# heat.net
KiCad netlist of a schematic drawn in Altium Designer
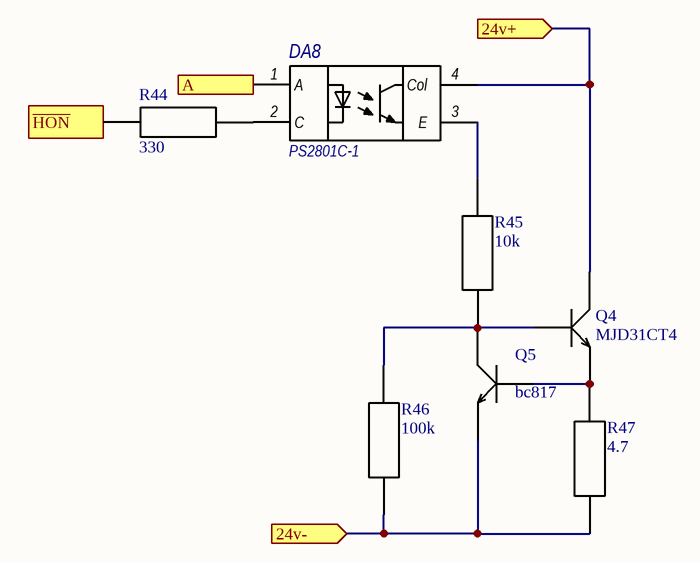
[diagram p0: heat.SchDoc]

(export (version "E")
  (design (tool "Eeschema 10.0.6"))
  (components
    (comp (ref "DA8")
      (value "PS2801C-1")
      (footprint "SSOP-4N")
      (fields (field (name "TYPE") "PS2801C-1"))
      (libsource (lib "Optocoupler") (part "PS2801C-1"))
    )
    (comp (ref "Q4")
      (value "MJD31CT4")
      (footprint "d-pak")
      (description "bc817")
      (libsource (lib "lib") (part "npn"))
    )
    (comp (ref "Q5") (value "bc817") (footprint "sot23") (libsource (lib "lib") (part "npn")))
    (comp (ref "R44") (value "330") (footprint "res_0402") (libsource (lib "lib") (part "res")))
    (comp (ref "R45") (value "10k") (footprint "Lib:0805-res") (libsource (lib "lib") (part "res")))
    (comp (ref "R46") (value "100k") (footprint "Lib:0805-res") (libsource (lib "lib") (part "res")))
    (comp (ref "R47") (value "4.7") (footprint "2512_res") (libsource (lib "lib") (part "res")))
  )
  (nets
    (net (code "1") (name "/24v+") (class "Default")
      (node (ref "DA8") (pin "4") (pinfunction "Col_4") (pintype "passive"))
      (node (ref "Q4") (pin "2") (pinfunction "K_2") (pintype "passive"))
    )
    (net (code "2") (name "/24v-") (class "Default")
      (node (ref "Q5") (pin "3") (pinfunction "E_3") (pintype "passive"))
      (node (ref "R46") (pin "1") (pinfunction "1_1") (pintype "passive"))
      (node (ref "R47") (pin "1") (pinfunction "1_1") (pintype "passive"))
    )
    (net (code "3") (name "/A") (class "Default")
      (node (ref "DA8") (pin "1") (pinfunction "A_1") (pintype "passive"))
    )
    (net (code "4") (name "/~{HON}") (class "Default")
      (node (ref "R44") (pin "1") (pinfunction "1_1") (pintype "passive"))
    )
    (net (code "5") (name "Net-(DA8-C)") (class "Default")
      (node (ref "DA8") (pin "2") (pinfunction "C_2") (pintype "passive"))
      (node (ref "R44") (pin "2") (pinfunction "2_2") (pintype "passive"))
    )
    (net (code "6") (name "Net-(DA8-E)") (class "Default")
      (node (ref "DA8") (pin "3") (pinfunction "E_3") (pintype "passive"))
      (node (ref "R45") (pin "2") (pinfunction "2_2") (pintype "passive"))
    )
    (net (code "7") (name "Net-(Q4-B)") (class "Default")
      (node (ref "Q4") (pin "1") (pinfunction "B_1") (pintype "passive"))
      (node (ref "Q5") (pin "2") (pinfunction "K_2") (pintype "passive"))
      (node (ref "R45") (pin "1") (pinfunction "1_1") (pintype "passive"))
      (node (ref "R46") (pin "2") (pinfunction "2_2") (pintype "passive"))
    )
    (net (code "8") (name "Net-(Q4-E)") (class "Default")
      (node (ref "Q4") (pin "3") (pinfunction "E_3") (pintype "passive"))
      (node (ref "Q5") (pin "1") (pinfunction "B_1") (pintype "passive"))
      (node (ref "R47") (pin "2") (pinfunction "2_2") (pintype "passive"))
    )
  )
)
